# FPGA_Power.net
KiCad netlist of a schematic drawn in Altium Designer
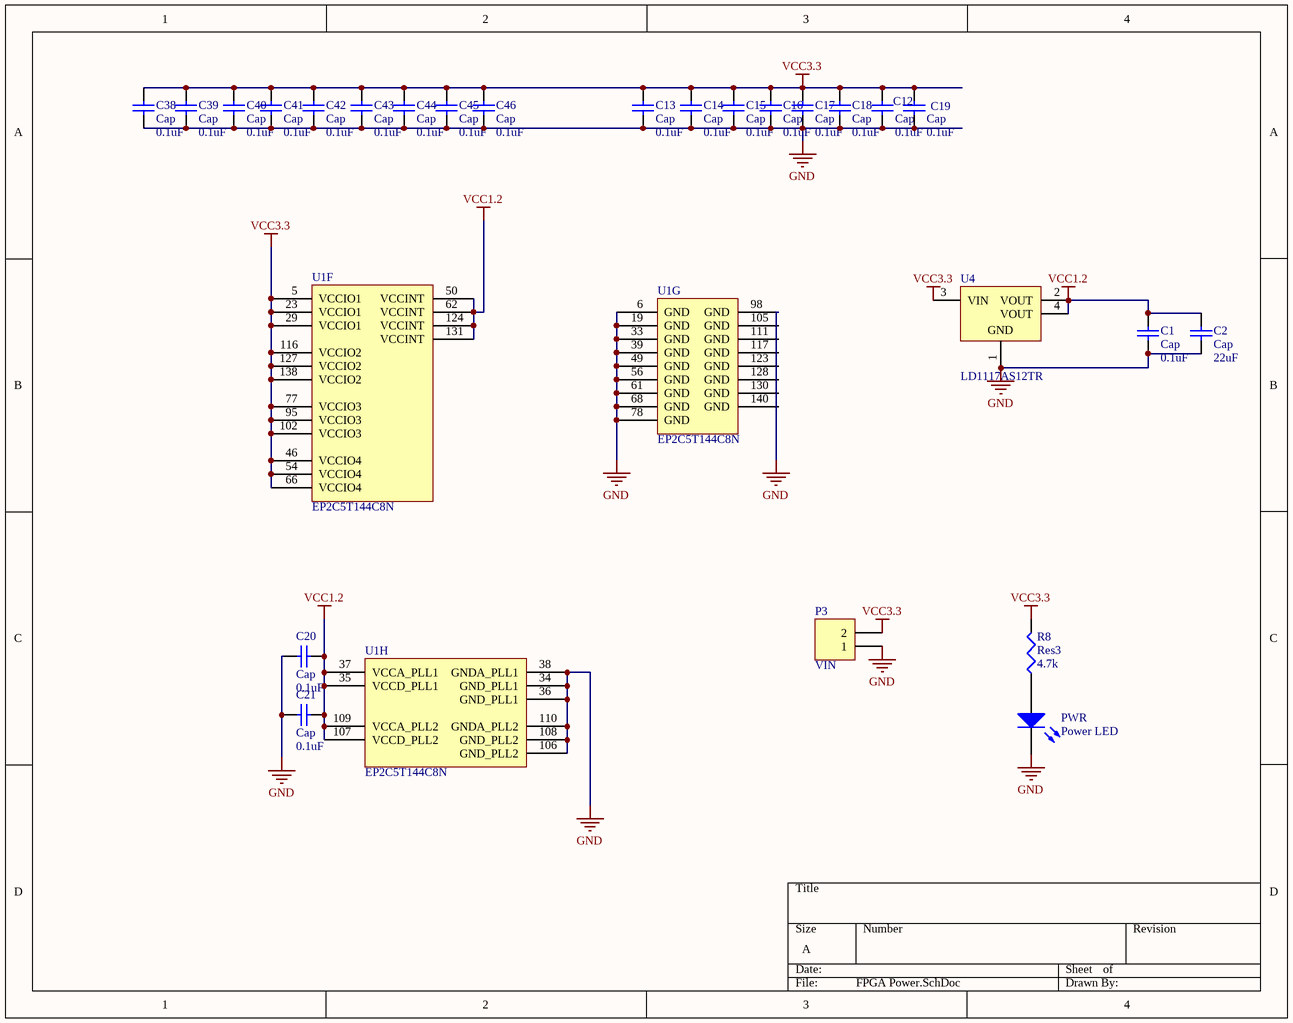
[diagram p0: FPGA Power.SchDoc]

(export (version "E")
  (design (tool "Eeschema 10.0.6"))
  (components
    (comp (ref "C1")
      (value "Cap")
      (footprint "1608[0603]")
      (description "Capacitor (Semiconductor SIM Model)")
      (fields (field (name "ALTIUM_VALUE") "0.1uF") (field (name "PUBLISHER") "Altium Limited"))
      (libsource (lib "Miscellaneous Devices") (part "Cap Semi"))
    )
    (comp (ref "C2")
      (value "Cap")
      (footprint "1608[0603]")
      (description "Capacitor (Semiconductor SIM Model)")
      (fields (field (name "ALTIUM_VALUE") "22uF") (field (name "PUBLISHER") "Altium Limited"))
      (libsource (lib "Miscellaneous Devices") (part "Cap Semi"))
    )
    (comp (ref "C12")
      (value "Cap")
      (footprint "1608[0603]")
      (description "Capacitor (Semiconductor SIM Model)")
      (fields (field (name "ALTIUM_VALUE") "0.1uF") (field (name "PUBLISHER") "Altium Limited"))
      (libsource (lib "Miscellaneous Devices") (part "Cap Semi"))
    )
    (comp (ref "C13")
      (value "Cap")
      (footprint "1608[0603]")
      (description "Capacitor (Semiconductor SIM Model)")
      (fields (field (name "ALTIUM_VALUE") "0.1uF") (field (name "PUBLISHER") "Altium Limited"))
      (libsource (lib "Miscellaneous Devices") (part "Cap Semi"))
    )
    (comp (ref "C14")
      (value "Cap")
      (footprint "1608[0603]")
      (description "Capacitor (Semiconductor SIM Model)")
      (fields (field (name "ALTIUM_VALUE") "0.1uF") (field (name "PUBLISHER") "Altium Limited"))
      (libsource (lib "Miscellaneous Devices") (part "Cap Semi"))
    )
    (comp (ref "C15")
      (value "Cap")
      (footprint "1608[0603]")
      (description "Capacitor (Semiconductor SIM Model)")
      (fields (field (name "ALTIUM_VALUE") "0.1uF") (field (name "PUBLISHER") "Altium Limited"))
      (libsource (lib "Miscellaneous Devices") (part "Cap Semi"))
    )
    (comp (ref "C16")
      (value "Cap")
      (footprint "1608[0603]")
      (description "Capacitor (Semiconductor SIM Model)")
      (fields (field (name "ALTIUM_VALUE") "0.1uF") (field (name "PUBLISHER") "Altium Limited"))
      (libsource (lib "Miscellaneous Devices") (part "Cap Semi"))
    )
    (comp (ref "C17")
      (value "Cap")
      (footprint "1608[0603]")
      (description "Capacitor (Semiconductor SIM Model)")
      (fields (field (name "ALTIUM_VALUE") "0.1uF") (field (name "PUBLISHER") "Altium Limited"))
      (libsource (lib "Miscellaneous Devices") (part "Cap Semi"))
    )
    (comp (ref "C18")
      (value "Cap")
      (footprint "1608[0603]")
      (description "Capacitor (Semiconductor SIM Model)")
      (fields (field (name "ALTIUM_VALUE") "0.1uF") (field (name "PUBLISHER") "Altium Limited"))
      (libsource (lib "Miscellaneous Devices") (part "Cap Semi"))
    )
    (comp (ref "C19")
      (value "Cap")
      (footprint "1608[0603]")
      (description "Capacitor (Semiconductor SIM Model)")
      (fields (field (name "ALTIUM_VALUE") "0.1uF") (field (name "PUBLISHER") "Altium Limited"))
      (libsource (lib "Miscellaneous Devices") (part "Cap Semi"))
    )
    (comp (ref "C20")
      (value "Cap")
      (footprint "1608[0603]")
      (description "Capacitor (Semiconductor SIM Model)")
      (fields (field (name "ALTIUM_VALUE") "0.1uF") (field (name "PUBLISHER") "Altium Limited"))
      (libsource (lib "Miscellaneous Devices") (part "Cap Semi"))
    )
    (comp (ref "C21")
      (value "Cap")
      (footprint "1608[0603]")
      (description "Capacitor (Semiconductor SIM Model)")
      (fields (field (name "ALTIUM_VALUE") "0.1uF") (field (name "PUBLISHER") "Altium Limited"))
      (libsource (lib "Miscellaneous Devices") (part "Cap Semi"))
    )
    (comp (ref "C38")
      (value "Cap")
      (footprint "1608[0603]")
      (description "Capacitor (Semiconductor SIM Model)")
      (fields (field (name "ALTIUM_VALUE") "0.1uF") (field (name "PUBLISHER") "Altium Limited"))
      (libsource (lib "Miscellaneous Devices") (part "Cap Semi"))
    )
    (comp (ref "C39")
      (value "Cap")
      (footprint "1608[0603]")
      (description "Capacitor (Semiconductor SIM Model)")
      (fields (field (name "ALTIUM_VALUE") "0.1uF") (field (name "PUBLISHER") "Altium Limited"))
      (libsource (lib "Miscellaneous Devices") (part "Cap Semi"))
    )
    (comp (ref "C40")
      (value "Cap")
      (footprint "1608[0603]")
      (description "Capacitor (Semiconductor SIM Model)")
      (fields (field (name "ALTIUM_VALUE") "0.1uF") (field (name "PUBLISHER") "Altium Limited"))
      (libsource (lib "Miscellaneous Devices") (part "Cap Semi"))
    )
    (comp (ref "C41")
      (value "Cap")
      (footprint "1608[0603]")
      (description "Capacitor (Semiconductor SIM Model)")
      (fields (field (name "ALTIUM_VALUE") "0.1uF") (field (name "PUBLISHER") "Altium Limited"))
      (libsource (lib "Miscellaneous Devices") (part "Cap Semi"))
    )
    (comp (ref "C42")
      (value "Cap")
      (footprint "1608[0603]")
      (description "Capacitor (Semiconductor SIM Model)")
      (fields (field (name "ALTIUM_VALUE") "0.1uF") (field (name "PUBLISHER") "Altium Limited"))
      (libsource (lib "Miscellaneous Devices") (part "Cap Semi"))
    )
    (comp (ref "C43")
      (value "Cap")
      (footprint "1608[0603]")
      (description "Capacitor (Semiconductor SIM Model)")
      (fields (field (name "ALTIUM_VALUE") "0.1uF") (field (name "PUBLISHER") "Altium Limited"))
      (libsource (lib "Miscellaneous Devices") (part "Cap Semi"))
    )
    (comp (ref "C44")
      (value "Cap")
      (footprint "1608[0603]")
      (description "Capacitor (Semiconductor SIM Model)")
      (fields (field (name "ALTIUM_VALUE") "0.1uF") (field (name "PUBLISHER") "Altium Limited"))
      (libsource (lib "Miscellaneous Devices") (part "Cap Semi"))
    )
    (comp (ref "C45")
      (value "Cap")
      (footprint "1608[0603]")
      (description "Capacitor (Semiconductor SIM Model)")
      (fields (field (name "ALTIUM_VALUE") "0.1uF") (field (name "PUBLISHER") "Altium Limited"))
      (libsource (lib "Miscellaneous Devices") (part "Cap Semi"))
    )
    (comp (ref "C46")
      (value "Cap")
      (footprint "1608[0603]")
      (description "Capacitor (Semiconductor SIM Model)")
      (fields (field (name "ALTIUM_VALUE") "0.1uF") (field (name "PUBLISHER") "Altium Limited"))
      (libsource (lib "Miscellaneous Devices") (part "Cap Semi"))
    )
    (comp (ref "P3")
      (value "VIN")
      (footprint "HDR1X2")
      (description "Header, 2-Pin")
      (fields (field (name "PUBLISHER") "Altium Limited"))
      (libsource (lib "Miscellaneous Connectors") (part "Header 2"))
    )
    (comp (ref "PWR")
      (value "Power LED")
      (footprint "1608[0603]")
      (description "Typical RED, GREEN, YELLOW, AMBER GaAs LED")
      (fields (field (name "PUBLISHER") "Altium Limited"))
      (libsource (lib "Miscellaneous Devices") (part "LED2"))
    )
    (comp (ref "R8")
      (value "Res3")
      (footprint "J1-0603")
      (description "Resistor")
      (fields (field (name "ALTIUM_VALUE") "4.7k") (field (name "PUBLISHER") "Altium Limited"))
      (libsource (lib "Miscellaneous Devices") (part "Res3"))
    )
    (comp (ref "U1")
      (value "EP2C5T144C8N")
      (footprint "TQFP144_N")
      (fields (field (name "PUBLISHER") "Altium Limited"))
      (libsource (lib "Altera Cyclone II") (part "EP2C5T144C8N"))
    )
    (comp (ref "U4")
      (value "LD1117AS12TR")
      (footprint "SOT223_M")
      (description "1A, Low Drop Positive Voltage Regulator, 1.2V, 4-Pin SOT-223, Tape and Reel")
      (libsource (lib "STMicroelectronics Power Management Linear Regulator") (part "LD1117AS12TR"))
    )
  )
  (nets
    (net (code "1") (name "GND") (class "Default")
      (node (ref "C1") (pin "1") (pinfunction "1_1") (pintype "passive"))
      (node (ref "C12") (pin "1") (pinfunction "1_1") (pintype "passive"))
      (node (ref "C13") (pin "1") (pinfunction "1_1") (pintype "passive"))
      (node (ref "C14") (pin "1") (pinfunction "1_1") (pintype "passive"))
      (node (ref "C15") (pin "1") (pinfunction "1_1") (pintype "passive"))
      (node (ref "C16") (pin "1") (pinfunction "1_1") (pintype "passive"))
      (node (ref "C17") (pin "1") (pinfunction "1_1") (pintype "passive"))
      (node (ref "C18") (pin "1") (pinfunction "1_1") (pintype "passive"))
      (node (ref "C19") (pin "1") (pinfunction "1_1") (pintype "passive"))
      (node (ref "C2") (pin "1") (pinfunction "1_1") (pintype "passive"))
      (node (ref "C20") (pin "1") (pinfunction "1_1") (pintype "passive"))
      (node (ref "C21") (pin "1") (pinfunction "1_1") (pintype "passive"))
      (node (ref "C38") (pin "1") (pinfunction "1_1") (pintype "passive"))
      (node (ref "C39") (pin "1") (pinfunction "1_1") (pintype "passive"))
      (node (ref "C40") (pin "1") (pinfunction "1_1") (pintype "passive"))
      (node (ref "C41") (pin "1") (pinfunction "1_1") (pintype "passive"))
      (node (ref "C42") (pin "1") (pinfunction "1_1") (pintype "passive"))
      (node (ref "C43") (pin "1") (pinfunction "1_1") (pintype "passive"))
      (node (ref "C44") (pin "1") (pinfunction "1_1") (pintype "passive"))
      (node (ref "C45") (pin "1") (pinfunction "1_1") (pintype "passive"))
      (node (ref "C46") (pin "1") (pinfunction "1_1") (pintype "passive"))
      (node (ref "P3") (pin "1") (pinfunction "1_1") (pintype "passive"))
      (node (ref "PWR") (pin "2") (pinfunction "K_2") (pintype "passive"))
      (node (ref "U1") (pin "106") (pinfunction "GND_PLL2_106") (pintype "power_in"))
      (node (ref "U1") (pin "108") (pinfunction "GND_PLL2_108") (pintype "power_in"))
      (node (ref "U1") (pin "110") (pinfunction "GNDA_PLL2_110") (pintype "power_in"))
      (node (ref "U1") (pin "19") (pinfunction "GND_19") (pintype "power_in"))
      (node (ref "U1") (pin "33") (pinfunction "GND_33") (pintype "power_in"))
      (node (ref "U1") (pin "34") (pinfunction "GND_PLL1_34") (pintype "power_in"))
      (node (ref "U1") (pin "36") (pinfunction "GND_PLL1_36") (pintype "power_in"))
      (node (ref "U1") (pin "38") (pinfunction "GNDA_PLL1_38") (pintype "power_in"))
      (node (ref "U1") (pin "39") (pinfunction "GND_39") (pintype "power_in"))
      (node (ref "U1") (pin "49") (pinfunction "GND_49") (pintype "power_in"))
      (node (ref "U1") (pin "56") (pinfunction "GND_56") (pintype "power_in"))
      (node (ref "U1") (pin "6") (pinfunction "GND_6") (pintype "power_in"))
      (node (ref "U1") (pin "61") (pinfunction "GND_61") (pintype "power_in"))
      (node (ref "U1") (pin "68") (pinfunction "GND_68") (pintype "power_in"))
      (node (ref "U1") (pin "78") (pinfunction "GND_78") (pintype "power_in"))
      (node (ref "U1") (pin "98") (pinfunction "GND_98") (pintype "power_in"))
      (node (ref "U4") (pin "1") (pinfunction "GND_1") (pintype "power_in"))
    )
    (net (code "2") (name "Net-(PWR-A)") (class "Default")
      (node (ref "PWR") (pin "1") (pinfunction "A_1") (pintype "passive"))
      (node (ref "R8") (pin "1") (pinfunction "1_1") (pintype "passive"))
    )
    (net (code "3") (name "VCC1.2") (class "Default")
      (node (ref "C1") (pin "2") (pinfunction "2_2") (pintype "passive"))
      (node (ref "C2") (pin "2") (pinfunction "2_2") (pintype "passive"))
      (node (ref "C20") (pin "2") (pinfunction "2_2") (pintype "passive"))
      (node (ref "C21") (pin "2") (pinfunction "2_2") (pintype "passive"))
      (node (ref "U1") (pin "107") (pinfunction "VCCD_PLL2_107") (pintype "power_in"))
      (node (ref "U1") (pin "109") (pinfunction "VCCA_PLL2_109") (pintype "power_in"))
      (node (ref "U1") (pin "124") (pinfunction "VCCINT_124") (pintype "power_in"))
      (node (ref "U1") (pin "131") (pinfunction "VCCINT_131") (pintype "power_in"))
      (node (ref "U1") (pin "35") (pinfunction "VCCD_PLL1_35") (pintype "power_in"))
      (node (ref "U1") (pin "37") (pinfunction "VCCA_PLL1_37") (pintype "power_in"))
      (node (ref "U1") (pin "50") (pinfunction "VCCINT_50") (pintype "power_in"))
      (node (ref "U1") (pin "62") (pinfunction "VCCINT_62") (pintype "power_in"))
      (node (ref "U4") (pin "2") (pinfunction "VOUT_2") (pintype "power_in"))
      (node (ref "U4") (pin "4") (pinfunction "VOUT_4") (pintype "power_in"))
    )
    (net (code "4") (name "VCC3.3") (class "Default")
      (node (ref "C12") (pin "2") (pinfunction "2_2") (pintype "passive"))
      (node (ref "C13") (pin "2") (pinfunction "2_2") (pintype "passive"))
      (node (ref "C14") (pin "2") (pinfunction "2_2") (pintype "passive"))
      (node (ref "C15") (pin "2") (pinfunction "2_2") (pintype "passive"))
      (node (ref "C16") (pin "2") (pinfunction "2_2") (pintype "passive"))
      (node (ref "C17") (pin "2") (pinfunction "2_2") (pintype "passive"))
      (node (ref "C18") (pin "2") (pinfunction "2_2") (pintype "passive"))
      (node (ref "C19") (pin "2") (pinfunction "2_2") (pintype "passive"))
      (node (ref "C38") (pin "2") (pinfunction "2_2") (pintype "passive"))
      (node (ref "C39") (pin "2") (pinfunction "2_2") (pintype "passive"))
      (node (ref "C40") (pin "2") (pinfunction "2_2") (pintype "passive"))
      (node (ref "C41") (pin "2") (pinfunction "2_2") (pintype "passive"))
      (node (ref "C42") (pin "2") (pinfunction "2_2") (pintype "passive"))
      (node (ref "C43") (pin "2") (pinfunction "2_2") (pintype "passive"))
      (node (ref "C44") (pin "2") (pinfunction "2_2") (pintype "passive"))
      (node (ref "C45") (pin "2") (pinfunction "2_2") (pintype "passive"))
      (node (ref "C46") (pin "2") (pinfunction "2_2") (pintype "passive"))
      (node (ref "P3") (pin "2") (pinfunction "2_2") (pintype "passive"))
      (node (ref "R8") (pin "2") (pinfunction "2_2") (pintype "passive"))
      (node (ref "U1") (pin "102") (pinfunction "VCCIO3_102") (pintype "power_in"))
      (node (ref "U1") (pin "116") (pinfunction "VCCIO2_116") (pintype "power_in"))
      (node (ref "U1") (pin "127") (pinfunction "VCCIO2_127") (pintype "power_in"))
      (node (ref "U1") (pin "138") (pinfunction "VCCIO2_138") (pintype "power_in"))
      (node (ref "U1") (pin "23") (pinfunction "VCCIO1_23") (pintype "power_in"))
      (node (ref "U1") (pin "29") (pinfunction "VCCIO1_29") (pintype "power_in"))
      (node (ref "U1") (pin "46") (pinfunction "VCCIO4_46") (pintype "power_in"))
      (node (ref "U1") (pin "5") (pinfunction "VCCIO1_5") (pintype "power_in"))
      (node (ref "U1") (pin "54") (pinfunction "VCCIO4_54") (pintype "power_in"))
      (node (ref "U1") (pin "66") (pinfunction "VCCIO4_66") (pintype "power_in"))
      (node (ref "U1") (pin "77") (pinfunction "VCCIO3_77") (pintype "power_in"))
      (node (ref "U1") (pin "95") (pinfunction "VCCIO3_95") (pintype "power_in"))
      (node (ref "U4") (pin "3") (pinfunction "VIN_3") (pintype "power_in"))
    )
    (net (code "5") (name "unconnected-(U1G-GND-Pad105)") (class "Default")
      (node (ref "U1") (pin "105") (pinfunction "GND_105") (pintype "power_in"))
    )
    (net (code "6") (name "unconnected-(U1G-GND-Pad111)") (class "Default")
      (node (ref "U1") (pin "111") (pinfunction "GND_111") (pintype "power_in"))
    )
    (net (code "7") (name "unconnected-(U1G-GND-Pad117)") (class "Default")
      (node (ref "U1") (pin "117") (pinfunction "GND_117") (pintype "power_in"))
    )
    (net (code "8") (name "unconnected-(U1G-GND-Pad123)") (class "Default")
      (node (ref "U1") (pin "123") (pinfunction "GND_123") (pintype "power_in"))
    )
    (net (code "9") (name "unconnected-(U1G-GND-Pad128)") (class "Default")
      (node (ref "U1") (pin "128") (pinfunction "GND_128") (pintype "power_in"))
    )
    (net (code "10") (name "unconnected-(U1G-GND-Pad130)") (class "Default")
      (node (ref "U1") (pin "130") (pinfunction "GND_130") (pintype "power_in"))
    )
    (net (code "11") (name "unconnected-(U1G-GND-Pad140)") (class "Default")
      (node (ref "U1") (pin "140") (pinfunction "GND_140") (pintype "power_in"))
    )
  )
)
